# I2C.net
KiCad netlist of a schematic drawn in Altium Designer
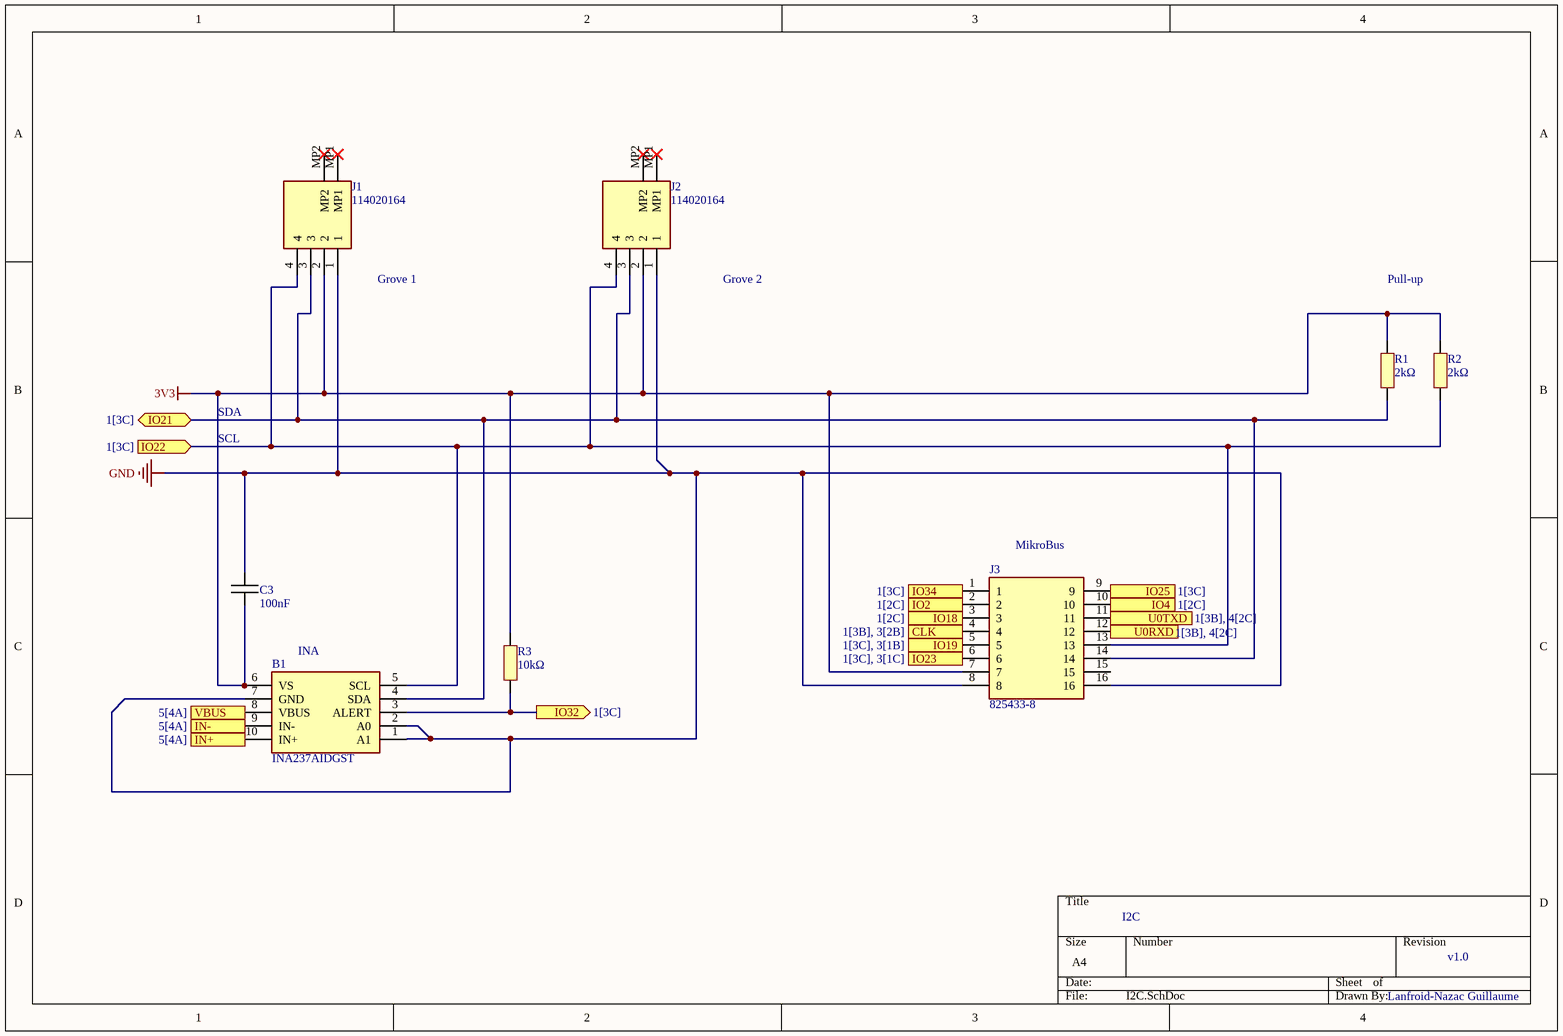
[diagram p0: I2C.SchDoc]

(export (version "E")
  (design (tool "Eeschema 10.0.6"))
  (components
    (comp (ref "B1")
      (value "INA237AIDGST")
      (footprint "SOP50P490X110-10N")
      (fields (field (name "MOUSER PART NUMBER") "595-INA237AIDGST"))
      (libsource (lib "SCHLibrary") (part "INA237AIDGST"))
    )
    (comp (ref "C3")
      (value "100nF")
      (footprint "CAPC1005X06N")
      (libsource (lib "SCHLibrary") (part "Capacitor"))
    )
    (comp (ref "J1")
      (value "114020164")
      (footprint "114020164")
      (description "Seeed Studio Accessories Grove Female Header - SMD-4P-2.0mm-90D-20Pcs")
      (fields (field (name "MOUSER PART NUMBER") "713-114020164"))
      (libsource (lib "SCHLibrary") (part "114020164"))
    )
    (comp (ref "J2")
      (value "114020164")
      (footprint "114020164")
      (description "Seeed Studio Accessories Grove Female Header - SMD-4P-2.0mm-90D-20Pcs")
      (fields (field (name "MOUSER PART NUMBER") "713-114020164"))
      (libsource (lib "SCHLibrary") (part "114020164"))
    )
    (comp (ref "J3")
      (value "825433-8")
      (footprint "Connect-Mikrobus")
      (description "Headers & Wire Housings 8P double for connection mikrobus")
      (fields (field (name "MOUSER PART NUMBER") "571-825433-8"))
      (libsource (lib "SCHLibrary") (part "Connect-Mikrobus"))
    )
    (comp (ref "R1")
      (value "2kΩ")
      (footprint "RESC1005X06N")
      (libsource (lib "SCHLibrary") (part "Resistor"))
    )
    (comp (ref "R2")
      (value "2kΩ")
      (footprint "RESC1005X06N")
      (libsource (lib "SCHLibrary") (part "Resistor"))
    )
    (comp (ref "R3")
      (value "10kΩ")
      (footprint "RESC1005X06N")
      (libsource (lib "SCHLibrary") (part "Resistor"))
    )
  )
  (nets
    (net (code "1") (name "/CLK") (class "Default")
      (node (ref "J3") (pin "4") (pinfunction "4_4") (pintype "passive"))
    )
    (net (code "2") (name "/IN+") (class "Default")
      (node (ref "B1") (pin "10") (pinfunction "IN+_10") (pintype "passive"))
    )
    (net (code "3") (name "/IN-") (class "Default")
      (node (ref "B1") (pin "9") (pinfunction "IN-_9") (pintype "passive"))
    )
    (net (code "4") (name "/IO2") (class "Default")
      (node (ref "J3") (pin "2") (pinfunction "2_2") (pintype "passive"))
    )
    (net (code "5") (name "/IO4") (class "Default")
      (node (ref "J3") (pin "10") (pinfunction "10_10") (pintype "passive"))
    )
    (net (code "6") (name "/IO18") (class "Default")
      (node (ref "J3") (pin "3") (pinfunction "3_3") (pintype "passive"))
    )
    (net (code "7") (name "/IO19") (class "Default")
      (node (ref "J3") (pin "5") (pinfunction "5_5") (pintype "passive"))
    )
    (net (code "8") (name "/IO21") (class "Default")
      (node (ref "B1") (pin "4") (pinfunction "SDA_4") (pintype "passive"))
      (node (ref "J1") (pin "3") (pinfunction "3_3") (pintype "passive"))
      (node (ref "J2") (pin "3") (pinfunction "3_3") (pintype "passive"))
      (node (ref "J3") (pin "14") (pinfunction "14_14") (pintype "passive"))
      (node (ref "R1") (pin "2") (pinfunction "2_2") (pintype "passive"))
    )
    (net (code "9") (name "/IO22") (class "Default")
      (node (ref "B1") (pin "5") (pinfunction "SCL_5") (pintype "passive"))
      (node (ref "J1") (pin "4") (pinfunction "4_4") (pintype "passive"))
      (node (ref "J2") (pin "4") (pinfunction "4_4") (pintype "passive"))
      (node (ref "J3") (pin "13") (pinfunction "13_13") (pintype "passive"))
      (node (ref "R2") (pin "2") (pinfunction "2_2") (pintype "passive"))
    )
    (net (code "10") (name "/IO23") (class "Default")
      (node (ref "J3") (pin "6") (pinfunction "6_6") (pintype "passive"))
    )
    (net (code "11") (name "/IO25") (class "Default")
      (node (ref "J3") (pin "9") (pinfunction "9_9") (pintype "passive"))
    )
    (net (code "12") (name "/IO32") (class "Default")
      (node (ref "B1") (pin "3") (pinfunction "ALERT_3") (pintype "passive"))
      (node (ref "R3") (pin "2") (pinfunction "2_2") (pintype "passive"))
    )
    (net (code "13") (name "/IO34") (class "Default")
      (node (ref "J3") (pin "1") (pinfunction "1_1") (pintype "passive"))
    )
    (net (code "14") (name "/U0RXD") (class "Default")
      (node (ref "J3") (pin "12") (pinfunction "12_12") (pintype "passive"))
    )
    (net (code "15") (name "/U0TXD") (class "Default")
      (node (ref "J3") (pin "11") (pinfunction "11_11") (pintype "passive"))
    )
    (net (code "16") (name "/VBUS") (class "Default")
      (node (ref "B1") (pin "8") (pinfunction "VBUS_8") (pintype "passive"))
    )
    (net (code "17") (name "3V3") (class "Default")
      (node (ref "B1") (pin "6") (pinfunction "VS_6") (pintype "passive"))
      (node (ref "C3") (pin "1") (pinfunction "1_1") (pintype "passive"))
      (node (ref "J1") (pin "2") (pinfunction "2_2") (pintype "passive"))
      (node (ref "J2") (pin "2") (pinfunction "2_2") (pintype "passive"))
      (node (ref "J3") (pin "7") (pinfunction "7_7") (pintype "passive"))
      (node (ref "R1") (pin "1") (pinfunction "1_1") (pintype "passive"))
      (node (ref "R2") (pin "1") (pinfunction "1_1") (pintype "passive"))
      (node (ref "R3") (pin "1") (pinfunction "1_1") (pintype "passive"))
    )
    (net (code "18") (name "GND") (class "Default")
      (node (ref "B1") (pin "1") (pinfunction "A1_1") (pintype "passive"))
      (node (ref "B1") (pin "2") (pinfunction "A0_2") (pintype "passive"))
      (node (ref "B1") (pin "7") (pinfunction "GND_7") (pintype "passive"))
      (node (ref "C3") (pin "2") (pinfunction "2_2") (pintype "passive"))
      (node (ref "J1") (pin "1") (pinfunction "1_1") (pintype "passive"))
      (node (ref "J2") (pin "1") (pinfunction "1_1") (pintype "passive"))
      (node (ref "J3") (pin "16") (pinfunction "16_16") (pintype "passive"))
      (node (ref "J3") (pin "8") (pinfunction "8_8") (pintype "passive"))
    )
    (net (code "19") (name "unconnected-(J1-PadMP1)") (class "Default")
      (node (ref "J1") (pin "MP1") (pinfunction "MP1_MP1") (pintype "passive+no_connect"))
    )
    (net (code "20") (name "unconnected-(J1-PadMP2)") (class "Default")
      (node (ref "J1") (pin "MP2") (pinfunction "MP2_MP2") (pintype "passive+no_connect"))
    )
    (net (code "21") (name "unconnected-(J2-PadMP1)") (class "Default")
      (node (ref "J2") (pin "MP1") (pinfunction "MP1_MP1") (pintype "passive+no_connect"))
    )
    (net (code "22") (name "unconnected-(J2-PadMP2)") (class "Default")
      (node (ref "J2") (pin "MP2") (pinfunction "MP2_MP2") (pintype "passive+no_connect"))
    )
    (net (code "23") (name "unconnected-(J3-Pad15)") (class "Default")
      (node (ref "J3") (pin "15") (pinfunction "15_15") (pintype "passive"))
    )
  )
)
